# S03_SOM1_A_B.net
KiCad netlist of a schematic drawn in Altium Designer
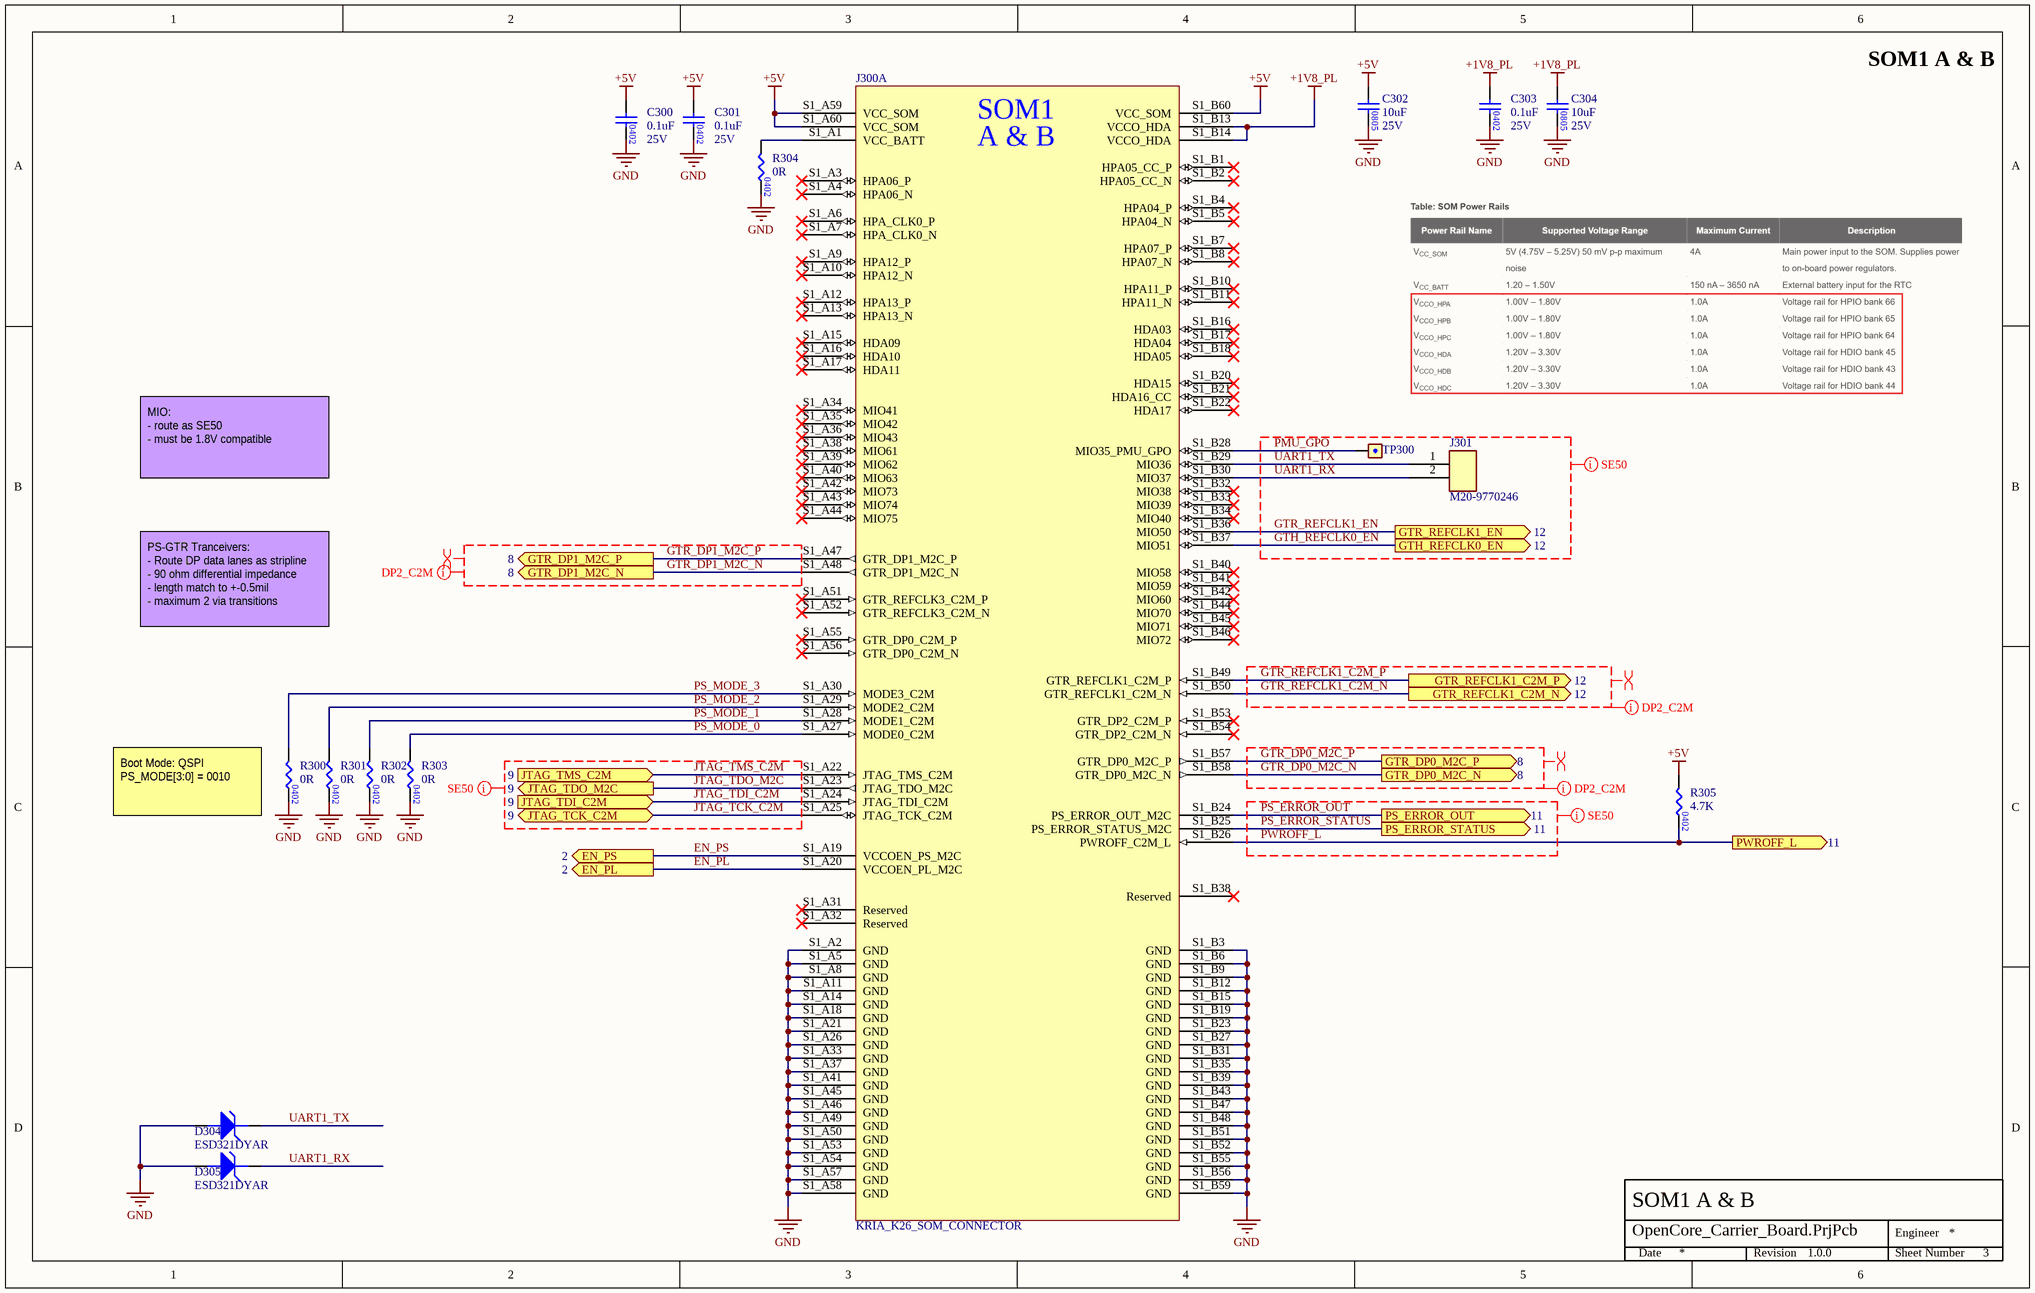
[diagram p0: S03_SOM1_A_B.SchDoc]

(export (version "E")
  (design (tool "Eeschema 10.0.6"))
  (components
    (comp (ref "C300")
      (value "0.1uF")
      (footprint "CAP0402")
      (description "CAP CER 0.1UF 25V X5R 0402")
      (fields
        (field (name "MANUFACTURER") "Samsung Electro-Mechanics")
        (field (name "TOLERANCE") "10%")
        (field (name "VOLTAGE RATING") "25V")
      )
      (libsource (lib "OpenCore_Sch_Lib") (part "CAP_CL05A104KA5NNNC"))
    )
    (comp (ref "C301")
      (value "0.1uF")
      (footprint "CAP0402")
      (description "CAP CER 0.1UF 25V X5R 0402")
      (fields
        (field (name "MANUFACTURER") "Samsung Electro-Mechanics")
        (field (name "TOLERANCE") "10%")
        (field (name "VOLTAGE RATING") "25V")
      )
      (libsource (lib "OpenCore_Sch_Lib") (part "CAP_CL05A104KA5NNNC"))
    )
    (comp (ref "C302")
      (value "10uF")
      (footprint "CAP0805")
      (description "CAP CER 10UF 25V X5R 0805")
      (fields
        (field (name "MANUFACTURER") "Samsung Electro-Mechanics")
        (field (name "TOLERANCE") "10%")
        (field (name "VOLTAGE RATING") "25V")
      )
      (libsource (lib "OpenCore_Sch_Lib") (part "CAP_CL21A106KAYNNNE"))
    )
    (comp (ref "C303")
      (value "0.1uF")
      (footprint "CAP0402")
      (description "CAP CER 0.1UF 25V X5R 0402")
      (fields
        (field (name "MANUFACTURER") "Samsung Electro-Mechanics")
        (field (name "TOLERANCE") "10%")
        (field (name "VOLTAGE RATING") "25V")
      )
      (libsource (lib "OpenCore_Sch_Lib") (part "CAP_CL05A104KA5NNNC"))
    )
    (comp (ref "C304")
      (value "10uF")
      (footprint "CAP0805")
      (description "CAP CER 10UF 25V X5R 0805")
      (fields
        (field (name "MANUFACTURER") "Samsung Electro-Mechanics")
        (field (name "TOLERANCE") "10%")
        (field (name "VOLTAGE RATING") "25V")
      )
      (libsource (lib "OpenCore_Sch_Lib") (part "CAP_CL21A106KAYNNNE"))
    )
    (comp (ref "D304")
      (value "ESD321DYAR")
      (footprint "TI_SOD523")
      (description "TVS DIODE 3.6VWM 6.3VC SOT5X3")
      (fields (field (name "MANFACTURER PART NUMBER") "ESD321DYAR"))
      (libsource (lib "OpenCore_Sch_Lib") (part "ESD321DYAR"))
    )
    (comp (ref "D305")
      (value "ESD321DYAR")
      (footprint "TI_SOD523")
      (description "TVS DIODE 3.6VWM 6.3VC SOT5X3")
      (fields (field (name "MANFACTURER PART NUMBER") "ESD321DYAR"))
      (libsource (lib "OpenCore_Sch_Lib") (part "ESD321DYAR"))
    )
    (comp (ref "J300")
      (value "KRIA_K26_SOM_CONNECTOR")
      (footprint "KRIA_K26_SOM")
      (description "2 x 240 pos Samtec REF-226081-01")
      (fields
        (field (name "MANUFACTURER") "Samtec")
        (field (name "MANUFACTURER PART NUMBER") "REF-226081-01")
      )
      (libsource (lib "OpenCore_Sch_Lib") (part "KRIA_K26_SOM"))
    )
    (comp (ref "J301")
      (value "M20-9770246")
      (footprint "61300211121")
      (description "CONN HEADER VERT 2POS 2.54MM")
      (libsource (lib "OpenCore_Sch_Lib") (part "M20-9770246"))
    )
    (comp (ref "R300")
      (value "RES_0402")
      (footprint "RES0402")
      (description "RES 0 OHM JUMPER 1/16W 0402")
      (fields
        (field (name "MANUFACTURER") "YAGEO")
        (field (name "MANUFACTURER PART NUMBER") "RC0402JR-070RL")
        (field (name "RESISTANCE") "0R")
      )
      (libsource (lib "OpenCore_Sch_Lib") (part ".RES_RC0402JR-070RL"))
    )
    (comp (ref "R301")
      (value "RES_0402")
      (footprint "RES0402")
      (description "RES 0 OHM JUMPER 1/16W 0402")
      (fields
        (field (name "MANUFACTURER") "YAGEO")
        (field (name "MANUFACTURER PART NUMBER") "RC0402JR-070RL")
        (field (name "RESISTANCE") "0R")
      )
      (libsource (lib "OpenCore_Sch_Lib") (part ".RES_RC0402JR-070RL"))
    )
    (comp (ref "R302")
      (value "RES_0402")
      (footprint "RES0402")
      (description "RES 0 OHM JUMPER 1/16W 0402")
      (fields
        (field (name "MANUFACTURER") "YAGEO")
        (field (name "MANUFACTURER PART NUMBER") "RC0402JR-070RL")
        (field (name "RESISTANCE") "0R")
      )
      (libsource (lib "OpenCore_Sch_Lib") (part ".RES_RC0402JR-070RL"))
    )
    (comp (ref "R303")
      (value "RES_0402")
      (footprint "RES0402")
      (description "RES 0 OHM JUMPER 1/16W 0402")
      (fields
        (field (name "MANUFACTURER") "YAGEO")
        (field (name "MANUFACTURER PART NUMBER") "RC0402JR-070RL")
        (field (name "RESISTANCE") "0R")
      )
      (libsource (lib "OpenCore_Sch_Lib") (part ".RES_RC0402JR-070RL"))
    )
    (comp (ref "R304")
      (value "RES_0402")
      (footprint "RES0402")
      (description "RES 0 OHM JUMPER 1/16W 0402")
      (fields
        (field (name "MANUFACTURER") "YAGEO")
        (field (name "MANUFACTURER PART NUMBER") "RC0402JR-070RL")
        (field (name "RESISTANCE") "0R")
      )
      (libsource (lib "OpenCore_Sch_Lib") (part ".RES_RC0402JR-070RL"))
    )
    (comp (ref "R305")
      (value "RES_0402")
      (footprint "RES0402")
      (description "RES 4.7K OHM 1% 1/16W 0402")
      (fields
        (field (name "MANUFACTURER") "YAGEO")
        (field (name "MANUFACTURER PART NUMBER") "RC0402FR-074K7L")
        (field (name "RESISTANCE") "4.7K")
      )
      (libsource (lib "OpenCore_Sch_Lib") (part ".RES_RC0402FR-074K7L"))
    )
    (comp (ref "TP300")
      (value "1mm Round Pad Testpoint")
      (footprint "TP_1MM")
      (libsource (lib "OpenCore_Sch_Lib") (part "TP_1MM"))
    )
  )
  (nets
    (net (code "1") (name "+1V8_PL") (class "Default")
      (node (ref "C303") (pin "1") (pinfunction "1_1") (pintype "passive"))
      (node (ref "C304") (pin "1") (pinfunction "1_1") (pintype "passive"))
      (node (ref "J300") (pin "S1_B13") (pinfunction "VCCO_HDA_S1_B13") (pintype "power_in"))
      (node (ref "J300") (pin "S1_B14") (pinfunction "VCCO_HDA_S1_B14") (pintype "power_in"))
    )
    (net (code "2") (name "+5V") (class "Default")
      (node (ref "C300") (pin "1") (pinfunction "1_1") (pintype "passive"))
      (node (ref "C301") (pin "1") (pinfunction "1_1") (pintype "passive"))
      (node (ref "C302") (pin "1") (pinfunction "1_1") (pintype "passive"))
      (node (ref "J300") (pin "S1_A59") (pinfunction "VCC_SOM_S1_A59") (pintype "power_in"))
      (node (ref "J300") (pin "S1_A60") (pinfunction "VCC_SOM_S1_A60") (pintype "power_in"))
      (node (ref "J300") (pin "S1_B60") (pinfunction "VCC_SOM_S1_B60") (pintype "power_in"))
      (node (ref "R305") (pin "1") (pinfunction "1_1") (pintype "passive"))
    )
    (net (code "3") (name "/EN_PL") (class "Default")
      (node (ref "J300") (pin "S1_A20") (pinfunction "VCCOEN_PL_M2C_S1_A20") (pintype "passive"))
    )
    (net (code "4") (name "/EN_PS") (class "Default")
      (node (ref "J300") (pin "S1_A19") (pinfunction "VCCOEN_PS_M2C_S1_A19") (pintype "passive"))
    )
    (net (code "5") (name "/GTH_REFCLK0_EN") (class "Default")
      (node (ref "J300") (pin "S1_B37") (pinfunction "MIO51_S1_B37") (pintype "bidirectional"))
    )
    (net (code "6") (name "/GTR_DP0_M2C_N") (class "Default")
      (node (ref "J300") (pin "S1_B58") (pinfunction "GTR_DP0_M2C_N_S1_B58") (pintype "output"))
    )
    (net (code "7") (name "/GTR_DP0_M2C_P") (class "Default")
      (node (ref "J300") (pin "S1_B57") (pinfunction "GTR_DP0_M2C_P_S1_B57") (pintype "output"))
    )
    (net (code "8") (name "/GTR_DP1_M2C_N") (class "Default")
      (node (ref "J300") (pin "S1_A48") (pinfunction "GTR_DP1_M2C_N_S1_A48") (pintype "output"))
    )
    (net (code "9") (name "/GTR_DP1_M2C_P") (class "Default")
      (node (ref "J300") (pin "S1_A47") (pinfunction "GTR_DP1_M2C_P_S1_A47") (pintype "output"))
    )
    (net (code "10") (name "/GTR_REFCLK1_C2M_N") (class "Default")
      (node (ref "J300") (pin "S1_B50") (pinfunction "GTR_REFCLK1_C2M_N_S1_B50") (pintype "input"))
    )
    (net (code "11") (name "/GTR_REFCLK1_C2M_P") (class "Default")
      (node (ref "J300") (pin "S1_B49") (pinfunction "GTR_REFCLK1_C2M_P_S1_B49") (pintype "input"))
    )
    (net (code "12") (name "/GTR_REFCLK1_EN") (class "Default")
      (node (ref "J300") (pin "S1_B36") (pinfunction "MIO50_S1_B36") (pintype "bidirectional"))
    )
    (net (code "13") (name "/JTAG_TCK_C2M") (class "Default")
      (node (ref "J300") (pin "S1_A25") (pinfunction "JTAG_TCK_C2M_S1_A25") (pintype "bidirectional"))
    )
    (net (code "14") (name "/JTAG_TDI_C2M") (class "Default")
      (node (ref "J300") (pin "S1_A24") (pinfunction "JTAG_TDI_C2M_S1_A24") (pintype "input"))
    )
    (net (code "15") (name "/JTAG_TDO_M2C") (class "Default")
      (node (ref "J300") (pin "S1_A23") (pinfunction "JTAG_TDO_M2C_S1_A23") (pintype "output"))
    )
    (net (code "16") (name "/JTAG_TMS_C2M") (class "Default")
      (node (ref "J300") (pin "S1_A22") (pinfunction "JTAG_TMS_C2M_S1_A22") (pintype "input"))
    )
    (net (code "17") (name "/PMU_GPO") (class "Default")
      (node (ref "J300") (pin "S1_B28") (pinfunction "MIO35_PMU_GPO_S1_B28") (pintype "bidirectional"))
      (node (ref "TP300") (pin "1") (pinfunction "1_1") (pintype "passive"))
    )
    (net (code "18") (name "/PS_ERROR_OUT") (class "Default")
      (node (ref "J300") (pin "S1_B24") (pinfunction "PS_ERROR_OUT_M2C_S1_B24") (pintype "passive"))
    )
    (net (code "19") (name "/PS_ERROR_STATUS") (class "Default")
      (node (ref "J300") (pin "S1_B25") (pinfunction "PS_ERROR_STATUS_M2C_S1_B25") (pintype "passive"))
    )
    (net (code "20") (name "/PS_MODE_0") (class "Default")
      (node (ref "J300") (pin "S1_A27") (pinfunction "MODE0_C2M_S1_A27") (pintype "input"))
      (node (ref "R303") (pin "1") (pinfunction "1_1") (pintype "passive"))
    )
    (net (code "21") (name "/PS_MODE_1") (class "Default")
      (node (ref "J300") (pin "S1_A28") (pinfunction "MODE1_C2M_S1_A28") (pintype "input"))
      (node (ref "R302") (pin "1") (pinfunction "1_1") (pintype "passive"))
    )
    (net (code "22") (name "/PS_MODE_2") (class "Default")
      (node (ref "J300") (pin "S1_A29") (pinfunction "MODE2_C2M_S1_A29") (pintype "input"))
      (node (ref "R301") (pin "1") (pinfunction "1_1") (pintype "passive"))
    )
    (net (code "23") (name "/PS_MODE_3") (class "Default")
      (node (ref "J300") (pin "S1_A30") (pinfunction "MODE3_C2M_S1_A30") (pintype "input"))
      (node (ref "R300") (pin "1") (pinfunction "1_1") (pintype "passive"))
    )
    (net (code "24") (name "/PWROFF_L") (class "Default")
      (node (ref "J300") (pin "S1_B26") (pinfunction "PWROFF_C2M_L_S1_B26") (pintype "input"))
      (node (ref "R305") (pin "2") (pinfunction "2_2") (pintype "passive"))
    )
    (net (code "25") (name "/UART1_RX") (class "Default")
      (node (ref "D305") (pin "K") (pinfunction "Cathode_K") (pintype "passive"))
      (node (ref "J300") (pin "S1_B30") (pinfunction "MIO37_S1_B30") (pintype "bidirectional"))
      (node (ref "J301") (pin "2") (pinfunction "2_2") (pintype "passive"))
    )
    (net (code "26") (name "/UART1_TX") (class "Default")
      (node (ref "D304") (pin "K") (pinfunction "Cathode_K") (pintype "passive"))
      (node (ref "J300") (pin "S1_B29") (pinfunction "MIO36_S1_B29") (pintype "bidirectional"))
      (node (ref "J301") (pin "1") (pinfunction "1_1") (pintype "passive"))
    )
    (net (code "27") (name "GND") (class "Default")
      (node (ref "C300") (pin "2") (pinfunction "2_2") (pintype "passive"))
      (node (ref "C301") (pin "2") (pinfunction "2_2") (pintype "passive"))
      (node (ref "C302") (pin "2") (pinfunction "2_2") (pintype "passive"))
      (node (ref "C303") (pin "2") (pinfunction "2_2") (pintype "passive"))
      (node (ref "C304") (pin "2") (pinfunction "2_2") (pintype "passive"))
      (node (ref "D304") (pin "A") (pinfunction "Anode_A") (pintype "passive"))
      (node (ref "D305") (pin "A") (pinfunction "Anode_A") (pintype "passive"))
      (node (ref "J300") (pin "S1_A11") (pinfunction "GND_S1_A11") (pintype "power_in"))
      (node (ref "J300") (pin "S1_A14") (pinfunction "GND_S1_A14") (pintype "power_in"))
      (node (ref "J300") (pin "S1_A18") (pinfunction "GND_S1_A18") (pintype "power_in"))
      (node (ref "J300") (pin "S1_A2") (pinfunction "GND_S1_A2") (pintype "power_in"))
      (node (ref "J300") (pin "S1_A21") (pinfunction "GND_S1_A21") (pintype "power_in"))
      (node (ref "J300") (pin "S1_A26") (pinfunction "GND_S1_A26") (pintype "power_in"))
      (node (ref "J300") (pin "S1_A33") (pinfunction "GND_S1_A33") (pintype "power_in"))
      (node (ref "J300") (pin "S1_A37") (pinfunction "GND_S1_A37") (pintype "power_in"))
      (node (ref "J300") (pin "S1_A41") (pinfunction "GND_S1_A41") (pintype "power_in"))
      (node (ref "J300") (pin "S1_A45") (pinfunction "GND_S1_A45") (pintype "power_in"))
      (node (ref "J300") (pin "S1_A46") (pinfunction "GND_S1_A46") (pintype "power_in"))
      (node (ref "J300") (pin "S1_A49") (pinfunction "GND_S1_A49") (pintype "power_in"))
      (node (ref "J300") (pin "S1_A5") (pinfunction "GND_S1_A5") (pintype "power_in"))
      (node (ref "J300") (pin "S1_A50") (pinfunction "GND_S1_A50") (pintype "power_in"))
      (node (ref "J300") (pin "S1_A53") (pinfunction "GND_S1_A53") (pintype "power_in"))
      (node (ref "J300") (pin "S1_A54") (pinfunction "GND_S1_A54") (pintype "power_in"))
      (node (ref "J300") (pin "S1_A57") (pinfunction "GND_S1_A57") (pintype "power_in"))
      (node (ref "J300") (pin "S1_A58") (pinfunction "GND_S1_A58") (pintype "power_in"))
      (node (ref "J300") (pin "S1_A8") (pinfunction "GND_S1_A8") (pintype "power_in"))
      (node (ref "J300") (pin "S1_B12") (pinfunction "GND_S1_B12") (pintype "power_in"))
      (node (ref "J300") (pin "S1_B15") (pinfunction "GND_S1_B15") (pintype "power_in"))
      (node (ref "J300") (pin "S1_B19") (pinfunction "GND_S1_B19") (pintype "power_in"))
      (node (ref "J300") (pin "S1_B23") (pinfunction "GND_S1_B23") (pintype "power_in"))
      (node (ref "J300") (pin "S1_B27") (pinfunction "GND_S1_B27") (pintype "power_in"))
      (node (ref "J300") (pin "S1_B3") (pinfunction "GND_S1_B3") (pintype "power_in"))
      (node (ref "J300") (pin "S1_B31") (pinfunction "GND_S1_B31") (pintype "power_in"))
      (node (ref "J300") (pin "S1_B35") (pinfunction "GND_S1_B35") (pintype "power_in"))
      (node (ref "J300") (pin "S1_B39") (pinfunction "GND_S1_B39") (pintype "power_in"))
      (node (ref "J300") (pin "S1_B43") (pinfunction "GND_S1_B43") (pintype "power_in"))
      (node (ref "J300") (pin "S1_B47") (pinfunction "GND_S1_B47") (pintype "power_in"))
      (node (ref "J300") (pin "S1_B48") (pinfunction "GND_S1_B48") (pintype "power_in"))
      (node (ref "J300") (pin "S1_B51") (pinfunction "GND_S1_B51") (pintype "power_in"))
      (node (ref "J300") (pin "S1_B52") (pinfunction "GND_S1_B52") (pintype "power_in"))
      (node (ref "J300") (pin "S1_B55") (pinfunction "GND_S1_B55") (pintype "power_in"))
      (node (ref "J300") (pin "S1_B56") (pinfunction "GND_S1_B56") (pintype "power_in"))
      (node (ref "J300") (pin "S1_B59") (pinfunction "GND_S1_B59") (pintype "power_in"))
      (node (ref "J300") (pin "S1_B6") (pinfunction "GND_S1_B6") (pintype "power_in"))
      (node (ref "J300") (pin "S1_B9") (pinfunction "GND_S1_B9") (pintype "power_in"))
      (node (ref "R300") (pin "2") (pinfunction "2_2") (pintype "passive"))
      (node (ref "R301") (pin "2") (pinfunction "2_2") (pintype "passive"))
      (node (ref "R302") (pin "2") (pinfunction "2_2") (pintype "passive"))
      (node (ref "R303") (pin "2") (pinfunction "2_2") (pintype "passive"))
      (node (ref "R304") (pin "2") (pinfunction "2_2") (pintype "passive"))
    )
    (net (code "28") (name "Net-(J300A-VCC_BATT)") (class "Default")
      (node (ref "J300") (pin "S1_A1") (pinfunction "VCC_BATT_S1_A1") (pintype "power_in"))
      (node (ref "R304") (pin "1") (pinfunction "1_1") (pintype "passive"))
    )
    (net (code "29") (name "unconnected-(J300A-GTR_DP0_C2M_N-PadS1_A56)") (class "Default")
      (node (ref "J300") (pin "S1_A56") (pinfunction "GTR_DP0_C2M_N_S1_A56") (pintype "input+no_connect"))
    )
    (net (code "30") (name "unconnected-(J300A-GTR_DP0_C2M_P-PadS1_A55)") (class "Default")
      (node (ref "J300") (pin "S1_A55") (pinfunction "GTR_DP0_C2M_P_S1_A55") (pintype "input+no_connect"))
    )
    (net (code "31") (name "unconnected-(J300A-GTR_DP2_C2M_N-PadS1_B54)") (class "Default")
      (node (ref "J300") (pin "S1_B54") (pinfunction "GTR_DP2_C2M_N_S1_B54") (pintype "input+no_connect"))
    )
    (net (code "32") (name "unconnected-(J300A-GTR_DP2_C2M_P-PadS1_B53)") (class "Default")
      (node (ref "J300") (pin "S1_B53") (pinfunction "GTR_DP2_C2M_P_S1_B53") (pintype "input+no_connect"))
    )
    (net (code "33") (name "unconnected-(J300A-GTR_REFCLK3_C2M_N-PadS1_A52)") (class "Default")
      (node (ref "J300") (pin "S1_A52") (pinfunction "GTR_REFCLK3_C2M_N_S1_A52") (pintype "input+no_connect"))
    )
    (net (code "34") (name "unconnected-(J300A-GTR_REFCLK3_C2M_P-PadS1_A51)") (class "Default")
      (node (ref "J300") (pin "S1_A51") (pinfunction "GTR_REFCLK3_C2M_P_S1_A51") (pintype "input+no_connect"))
    )
    (net (code "35") (name "unconnected-(J300A-HDA03-PadS1_B16)") (class "Default")
      (node (ref "J300") (pin "S1_B16") (pinfunction "HDA03_S1_B16") (pintype "bidirectional+no_connect"))
    )
    (net (code "36") (name "unconnected-(J300A-HDA04-PadS1_B17)") (class "Default")
      (node (ref "J300") (pin "S1_B17") (pinfunction "HDA04_S1_B17") (pintype "bidirectional+no_connect"))
    )
    (net (code "37") (name "unconnected-(J300A-HDA05-PadS1_B18)") (class "Default")
      (node (ref "J300") (pin "S1_B18") (pinfunction "HDA05_S1_B18") (pintype "bidirectional+no_connect"))
    )
    (net (code "38") (name "unconnected-(J300A-HDA09-PadS1_A15)") (class "Default")
      (node (ref "J300") (pin "S1_A15") (pinfunction "HDA09_S1_A15") (pintype "bidirectional+no_connect"))
    )
    (net (code "39") (name "unconnected-(J300A-HDA10-PadS1_A16)") (class "Default")
      (node (ref "J300") (pin "S1_A16") (pinfunction "HDA10_S1_A16") (pintype "bidirectional+no_connect"))
    )
    (net (code "40") (name "unconnected-(J300A-HDA11-PadS1_A17)") (class "Default")
      (node (ref "J300") (pin "S1_A17") (pinfunction "HDA11_S1_A17") (pintype "bidirectional+no_connect"))
    )
    (net (code "41") (name "unconnected-(J300A-HDA15-PadS1_B20)") (class "Default")
      (node (ref "J300") (pin "S1_B20") (pinfunction "HDA15_S1_B20") (pintype "bidirectional+no_connect"))
    )
    (net (code "42") (name "unconnected-(J300A-HDA16_CC-PadS1_B21)") (class "Default")
      (node (ref "J300") (pin "S1_B21") (pinfunction "HDA16_CC_S1_B21") (pintype "bidirectional+no_connect"))
    )
    (net (code "43") (name "unconnected-(J300A-HDA17-PadS1_B22)") (class "Default")
      (node (ref "J300") (pin "S1_B22") (pinfunction "HDA17_S1_B22") (pintype "bidirectional+no_connect"))
    )
    (net (code "44") (name "unconnected-(J300A-HPA04_N-PadS1_B5)") (class "Default")
      (node (ref "J300") (pin "S1_B5") (pinfunction "HPA04_N_S1_B5") (pintype "bidirectional+no_connect"))
    )
    (net (code "45") (name "unconnected-(J300A-HPA04_P-PadS1_B4)") (class "Default")
      (node (ref "J300") (pin "S1_B4") (pinfunction "HPA04_P_S1_B4") (pintype "bidirectional+no_connect"))
    )
    (net (code "46") (name "unconnected-(J300A-HPA05_CC_N-PadS1_B2)") (class "Default")
      (node (ref "J300") (pin "S1_B2") (pinfunction "HPA05_CC_N_S1_B2") (pintype "bidirectional+no_connect"))
    )
    (net (code "47") (name "unconnected-(J300A-HPA05_CC_P-PadS1_B1)") (class "Default")
      (node (ref "J300") (pin "S1_B1") (pinfunction "HPA05_CC_P_S1_B1") (pintype "bidirectional+no_connect"))
    )
    (net (code "48") (name "unconnected-(J300A-HPA06_N-PadS1_A4)") (class "Default")
      (node (ref "J300") (pin "S1_A4") (pinfunction "HPA06_N_S1_A4") (pintype "bidirectional+no_connect"))
    )
    (net (code "49") (name "unconnected-(J300A-HPA06_P-PadS1_A3)") (class "Default")
      (node (ref "J300") (pin "S1_A3") (pinfunction "HPA06_P_S1_A3") (pintype "bidirectional+no_connect"))
    )
    (net (code "50") (name "unconnected-(J300A-HPA07_N-PadS1_B8)") (class "Default")
      (node (ref "J300") (pin "S1_B8") (pinfunction "HPA07_N_S1_B8") (pintype "bidirectional+no_connect"))
    )
    (net (code "51") (name "unconnected-(J300A-HPA07_P-PadS1_B7)") (class "Default")
      (node (ref "J300") (pin "S1_B7") (pinfunction "HPA07_P_S1_B7") (pintype "bidirectional+no_connect"))
    )
    (net (code "52") (name "unconnected-(J300A-HPA11_N-PadS1_B11)") (class "Default")
      (node (ref "J300") (pin "S1_B11") (pinfunction "HPA11_N_S1_B11") (pintype "bidirectional+no_connect"))
    )
    (net (code "53") (name "unconnected-(J300A-HPA11_P-PadS1_B10)") (class "Default")
      (node (ref "J300") (pin "S1_B10") (pinfunction "HPA11_P_S1_B10") (pintype "bidirectional+no_connect"))
    )
    (net (code "54") (name "unconnected-(J300A-HPA12_N-PadS1_A10)") (class "Default")
      (node (ref "J300") (pin "S1_A10") (pinfunction "HPA12_N_S1_A10") (pintype "bidirectional+no_connect"))
    )
    (net (code "55") (name "unconnected-(J300A-HPA12_P-PadS1_A9)") (class "Default")
      (node (ref "J300") (pin "S1_A9") (pinfunction "HPA12_P_S1_A9") (pintype "bidirectional+no_connect"))
    )
    (net (code "56") (name "unconnected-(J300A-HPA13_N-PadS1_A13)") (class "Default")
      (node (ref "J300") (pin "S1_A13") (pinfunction "HPA13_N_S1_A13") (pintype "bidirectional+no_connect"))
    )
    (net (code "57") (name "unconnected-(J300A-HPA13_P-PadS1_A12)") (class "Default")
      (node (ref "J300") (pin "S1_A12") (pinfunction "HPA13_P_S1_A12") (pintype "bidirectional+no_connect"))
    )
    (net (code "58") (name "unconnected-(J300A-HPA_CLK0_N-PadS1_A7)") (class "Default")
      (node (ref "J300") (pin "S1_A7") (pinfunction "HPA_CLK0_N_S1_A7") (pintype "bidirectional+no_connect"))
    )
    (net (code "59") (name "unconnected-(J300A-HPA_CLK0_P-PadS1_A6)") (class "Default")
      (node (ref "J300") (pin "S1_A6") (pinfunction "HPA_CLK0_P_S1_A6") (pintype "bidirectional+no_connect"))
    )
    (net (code "60") (name "unconnected-(J300A-MIO38-PadS1_B32)") (class "Default")
      (node (ref "J300") (pin "S1_B32") (pinfunction "MIO38_S1_B32") (pintype "bidirectional+no_connect"))
    )
    (net (code "61") (name "unconnected-(J300A-MIO39-PadS1_B33)") (class "Default")
      (node (ref "J300") (pin "S1_B33") (pinfunction "MIO39_S1_B33") (pintype "bidirectional+no_connect"))
    )
    (net (code "62") (name "unconnected-(J300A-MIO40-PadS1_B34)") (class "Default")
      (node (ref "J300") (pin "S1_B34") (pinfunction "MIO40_S1_B34") (pintype "bidirectional+no_connect"))
    )
    (net (code "63") (name "unconnected-(J300A-MIO41-PadS1_A34)") (class "Default")
      (node (ref "J300") (pin "S1_A34") (pinfunction "MIO41_S1_A34") (pintype "bidirectional+no_connect"))
    )
    (net (code "64") (name "unconnected-(J300A-MIO42-PadS1_A35)") (class "Default")
      (node (ref "J300") (pin "S1_A35") (pinfunction "MIO42_S1_A35") (pintype "bidirectional+no_connect"))
    )
    (net (code "65") (name "unconnected-(J300A-MIO43-PadS1_A36)") (class "Default")
      (node (ref "J300") (pin "S1_A36") (pinfunction "MIO43_S1_A36") (pintype "bidirectional+no_connect"))
    )
    (net (code "66") (name "unconnected-(J300A-MIO58-PadS1_B40)") (class "Default")
      (node (ref "J300") (pin "S1_B40") (pinfunction "MIO58_S1_B40") (pintype "bidirectional+no_connect"))
    )
    (net (code "67") (name "unconnected-(J300A-MIO59-PadS1_B41)") (class "Default")
      (node (ref "J300") (pin "S1_B41") (pinfunction "MIO59_S1_B41") (pintype "bidirectional+no_connect"))
    )
    (net (code "68") (name "unconnected-(J300A-MIO60-PadS1_B42)") (class "Default")
      (node (ref "J300") (pin "S1_B42") (pinfunction "MIO60_S1_B42") (pintype "bidirectional+no_connect"))
    )
    (net (code "69") (name "unconnected-(J300A-MIO61-PadS1_A38)") (class "Default")
      (node (ref "J300") (pin "S1_A38") (pinfunction "MIO61_S1_A38") (pintype "bidirectional+no_connect"))
    )
    (net (code "70") (name "unconnected-(J300A-MIO62-PadS1_A39)") (class "Default")
      (node (ref "J300") (pin "S1_A39") (pinfunction "MIO62_S1_A39") (pintype "bidirectional+no_connect"))
    )
    (net (code "71") (name "unconnected-(J300A-MIO63-PadS1_A40)") (class "Default")
      (node (ref "J300") (pin "S1_A40") (pinfunction "MIO63_S1_A40") (pintype "bidirectional+no_connect"))
    )
    (net (code "72") (name "unconnected-(J300A-MIO70-PadS1_B44)") (class "Default")
      (node (ref "J300") (pin "S1_B44") (pinfunction "MIO70_S1_B44") (pintype "bidirectional+no_connect"))
    )
    (net (code "73") (name "unconnected-(J300A-MIO71-PadS1_B45)") (class "Default")
      (node (ref "J300") (pin "S1_B45") (pinfunction "MIO71_S1_B45") (pintype "bidirectional+no_connect"))
    )
    (net (code "74") (name "unconnected-(J300A-MIO72-PadS1_B46)") (class "Default")
      (node (ref "J300") (pin "S1_B46") (pinfunction "MIO72_S1_B46") (pintype "bidirectional+no_connect"))
    )
    (net (code "75") (name "unconnected-(J300A-MIO73-PadS1_A42)") (class "Default")
      (node (ref "J300") (pin "S1_A42") (pinfunction "MIO73_S1_A42") (pintype "bidirectional+no_connect"))
    )
    (net (code "76") (name "unconnected-(J300A-MIO74-PadS1_A43)") (class "Default")
      (node (ref "J300") (pin "S1_A43") (pinfunction "MIO74_S1_A43") (pintype "bidirectional+no_connect"))
    )
    (net (code "77") (name "unconnected-(J300A-MIO75-PadS1_A44)") (class "Default")
      (node (ref "J300") (pin "S1_A44") (pinfunction "MIO75_S1_A44") (pintype "bidirectional+no_connect"))
    )
    (net (code "78") (name "unconnected-(J300A-Reserved-PadS1_A31)") (class "Default")
      (node (ref "J300") (pin "S1_A31") (pinfunction "Reserved_S1_A31") (pintype "passive+no_connect"))
    )
    (net (code "79") (name "unconnected-(J300A-Reserved-PadS1_A32)") (class "Default")
      (node (ref "J300") (pin "S1_A32") (pinfunction "Reserved_S1_A32") (pintype "passive+no_connect"))
    )
    (net (code "80") (name "unconnected-(J300A-Reserved-PadS1_B38)") (class "Default")
      (node (ref "J300") (pin "S1_B38") (pinfunction "Reserved_S1_B38") (pintype "passive+no_connect"))
    )
  )
)
